# RN41-v14.net
KiCad netlist of a schematic drawn in EAGLE
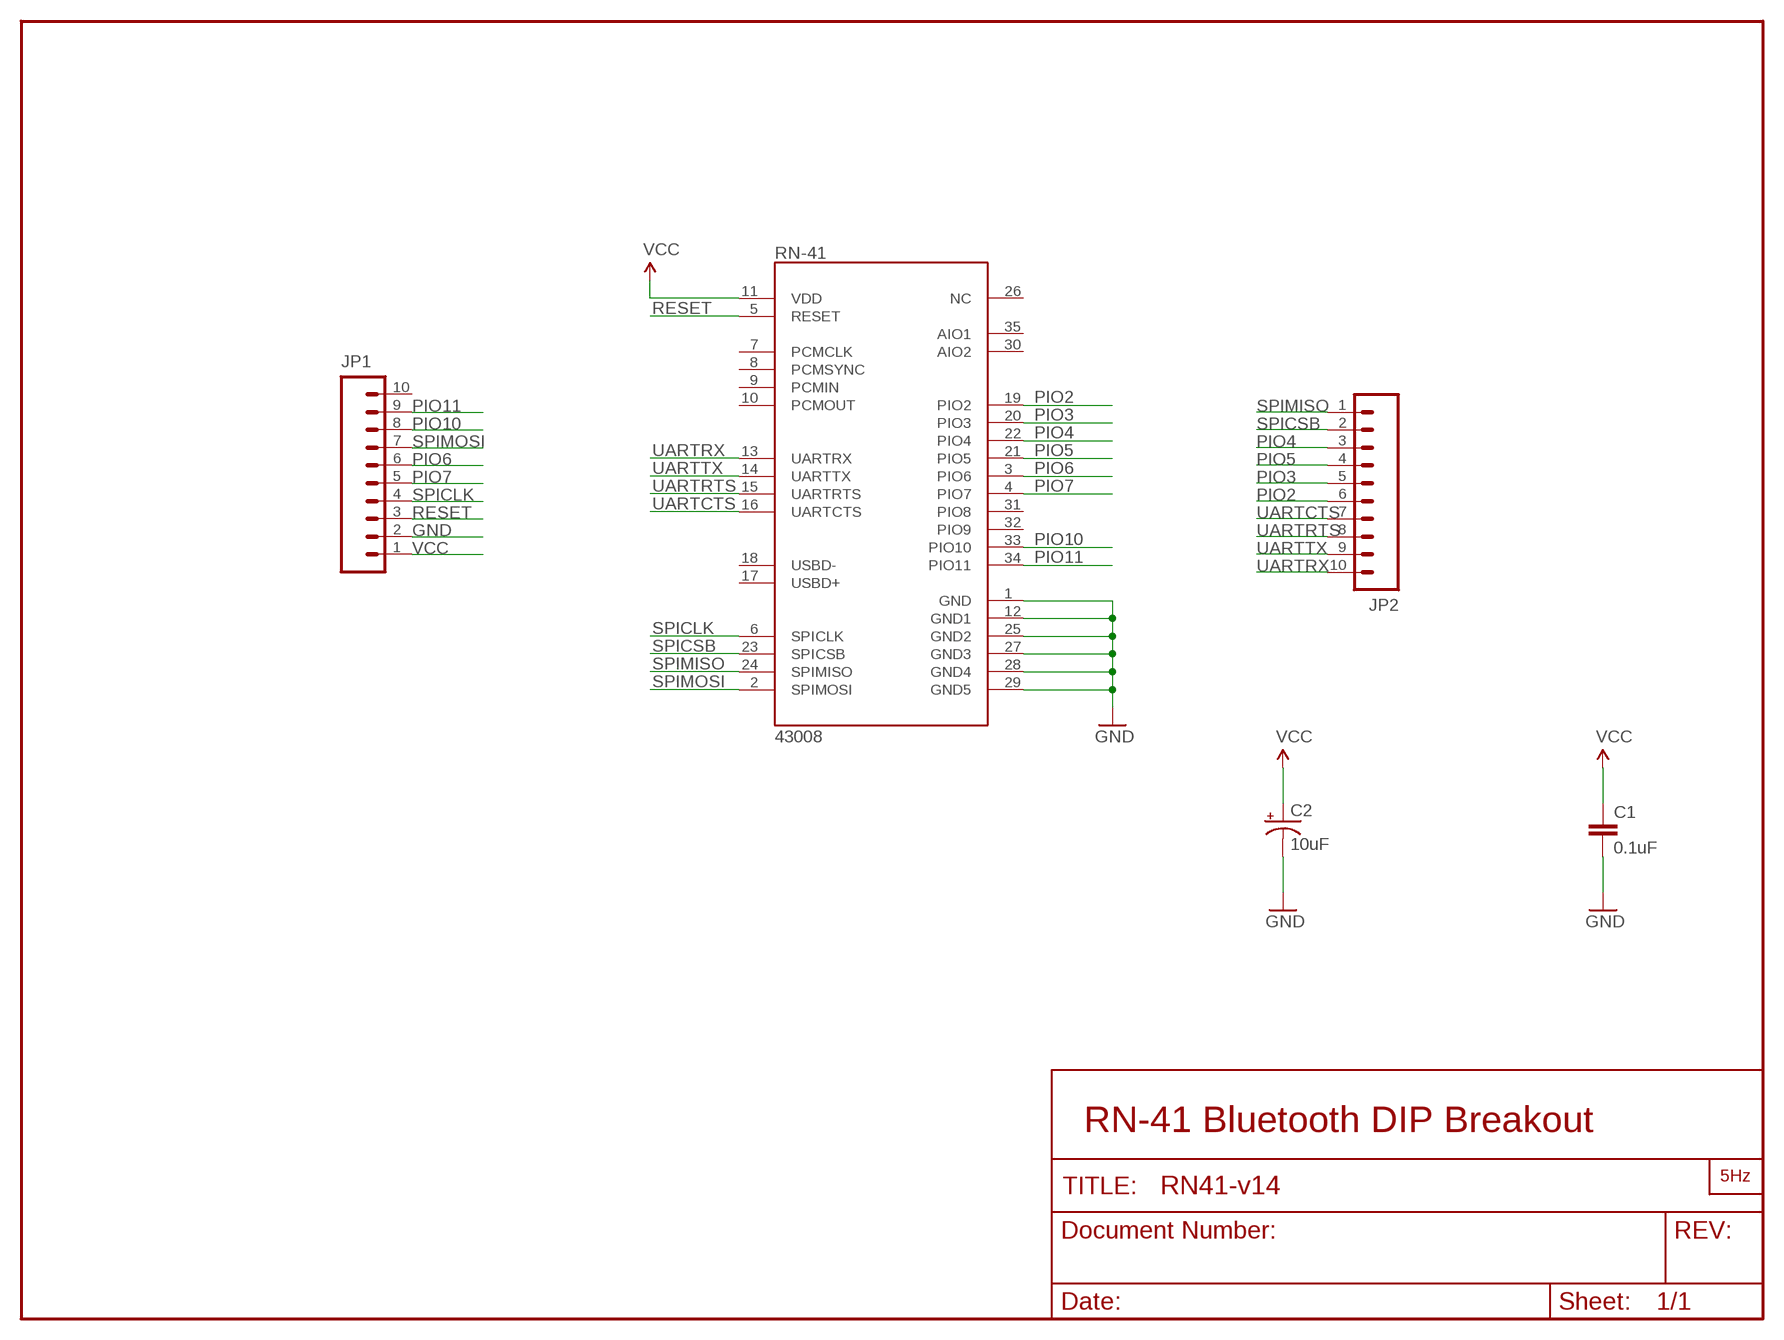
[diagram p0: schematic, sheet 1]

(export (version "E")
  (design (tool "Eeschema 10.0.6"))
  (components
    (comp (ref "C1")
      (value "0.1uF")
      (footprint "eagle-import:0603-CAP")
      (libsource (lib "eagle-import") (part "CAP0603-CAP"))
    )
    (comp (ref "C2")
      (value "10uF")
      (footprint "eagle-import:EIA3216")
      (libsource (lib "eagle-import") (part "CAP_POL1206"))
    )
    (comp (ref "JP1")
      (value "M10\"")
      (footprint "eagle-import:1X10")
      (libsource (lib "eagle-import") (part "M10{dblquote}"))
    )
    (comp (ref "JP2")
      (value "M10\"")
      (footprint "eagle-import:1X10")
      (libsource (lib "eagle-import") (part "M10{dblquote}"))
    )
    (comp (ref "RN-41")
      (value "43008")
      (footprint "eagle-import:RN41")
      (libsource (lib "eagle-import") (part "BLUETOOTH-RN41{dblquote}"))
    )
    (comp (ref "U$1")
      (value "LOGO2_SILKL10MM")
      (footprint "eagle-import:LARGO2_10MM")
      (libsource (lib "eagle-import") (part "LOGO2_SILKL10MM"))
    )
  )
  (nets
    (net (code "1") (name "/PIO2") (class "Default")
      (node (ref "JP2") (pin "6") (pinfunction "6_6") (pintype "passive"))
      (node (ref "RN-41") (pin "19") (pinfunction "PIO2_19") (pintype "bidirectional"))
    )
    (net (code "2") (name "/PIO3") (class "Default")
      (node (ref "JP2") (pin "5") (pinfunction "5_5") (pintype "passive"))
      (node (ref "RN-41") (pin "20") (pinfunction "PIO3_20") (pintype "bidirectional"))
    )
    (net (code "3") (name "/PIO4") (class "Default")
      (node (ref "JP2") (pin "3") (pinfunction "3_3") (pintype "passive"))
      (node (ref "RN-41") (pin "22") (pinfunction "PIO4_22") (pintype "bidirectional"))
    )
    (net (code "4") (name "/PIO5") (class "Default")
      (node (ref "JP2") (pin "4") (pinfunction "4_4") (pintype "passive"))
      (node (ref "RN-41") (pin "21") (pinfunction "PIO5_21") (pintype "bidirectional"))
    )
    (net (code "5") (name "/PIO6") (class "Default")
      (node (ref "JP1") (pin "6") (pinfunction "6_6") (pintype "passive"))
      (node (ref "RN-41") (pin "3") (pinfunction "PIO6_3") (pintype "bidirectional"))
    )
    (net (code "6") (name "/PIO7") (class "Default")
      (node (ref "JP1") (pin "5") (pinfunction "5_5") (pintype "passive"))
      (node (ref "RN-41") (pin "4") (pinfunction "PIO7_4") (pintype "bidirectional"))
    )
    (net (code "7") (name "/PIO10") (class "Default")
      (node (ref "JP1") (pin "8") (pinfunction "8_8") (pintype "passive"))
      (node (ref "RN-41") (pin "33") (pinfunction "PIO10_33") (pintype "bidirectional"))
    )
    (net (code "8") (name "/PIO11") (class "Default")
      (node (ref "JP1") (pin "9") (pinfunction "9_9") (pintype "passive"))
      (node (ref "RN-41") (pin "34") (pinfunction "PIO11_34") (pintype "bidirectional"))
    )
    (net (code "9") (name "/RESET") (class "Default")
      (node (ref "JP1") (pin "3") (pinfunction "3_3") (pintype "passive"))
      (node (ref "RN-41") (pin "5") (pinfunction "RESET_5") (pintype "bidirectional"))
    )
    (net (code "10") (name "/SPICLK") (class "Default")
      (node (ref "JP1") (pin "4") (pinfunction "4_4") (pintype "passive"))
      (node (ref "RN-41") (pin "6") (pinfunction "SPICLK_6") (pintype "bidirectional"))
    )
    (net (code "11") (name "/SPICSB") (class "Default")
      (node (ref "JP2") (pin "2") (pinfunction "2_2") (pintype "passive"))
      (node (ref "RN-41") (pin "23") (pinfunction "SPICSB_23") (pintype "bidirectional"))
    )
    (net (code "12") (name "/SPIMISO") (class "Default")
      (node (ref "JP2") (pin "1") (pinfunction "1_1") (pintype "passive"))
      (node (ref "RN-41") (pin "24") (pinfunction "SPIMISO_24") (pintype "bidirectional"))
    )
    (net (code "13") (name "/SPIMOSI") (class "Default")
      (node (ref "JP1") (pin "7") (pinfunction "7_7") (pintype "passive"))
      (node (ref "RN-41") (pin "2") (pinfunction "SPIMOSI_2") (pintype "bidirectional"))
    )
    (net (code "14") (name "/UARTCTS") (class "Default")
      (node (ref "JP2") (pin "7") (pinfunction "7_7") (pintype "passive"))
      (node (ref "RN-41") (pin "16") (pinfunction "UARTCTS_16") (pintype "bidirectional"))
    )
    (net (code "15") (name "/UARTRTS") (class "Default")
      (node (ref "JP2") (pin "8") (pinfunction "8_8") (pintype "passive"))
      (node (ref "RN-41") (pin "15") (pinfunction "UARTRTS_15") (pintype "bidirectional"))
    )
    (net (code "16") (name "/UARTRX") (class "Default")
      (node (ref "JP2") (pin "10") (pinfunction "10_10") (pintype "passive"))
      (node (ref "RN-41") (pin "13") (pinfunction "UARTRX_13") (pintype "bidirectional"))
    )
    (net (code "17") (name "/UARTTX") (class "Default")
      (node (ref "JP2") (pin "9") (pinfunction "9_9") (pintype "passive"))
      (node (ref "RN-41") (pin "14") (pinfunction "UARTTX_14") (pintype "bidirectional"))
    )
    (net (code "18") (name "GND") (class "Default")
      (node (ref "C1") (pin "2") (pinfunction "2_2") (pintype "passive"))
      (node (ref "C2") (pin "C") (pinfunction "-_C") (pintype "passive"))
      (node (ref "JP1") (pin "2") (pinfunction "2_2") (pintype "passive"))
      (node (ref "RN-41") (pin "1") (pinfunction "GND_1") (pintype "bidirectional"))
      (node (ref "RN-41") (pin "12") (pinfunction "GND1_12") (pintype "bidirectional"))
      (node (ref "RN-41") (pin "25") (pinfunction "GND2_25") (pintype "bidirectional"))
      (node (ref "RN-41") (pin "27") (pinfunction "GND3_27") (pintype "bidirectional"))
      (node (ref "RN-41") (pin "28") (pinfunction "GND4_28") (pintype "bidirectional"))
      (node (ref "RN-41") (pin "29") (pinfunction "GND5_29") (pintype "bidirectional"))
    )
    (net (code "19") (name "VCC") (class "Default")
      (node (ref "C1") (pin "1") (pinfunction "1_1") (pintype "passive"))
      (node (ref "C2") (pin "A") (pinfunction "+_A") (pintype "passive"))
      (node (ref "JP1") (pin "1") (pinfunction "1_1") (pintype "passive"))
      (node (ref "RN-41") (pin "11") (pinfunction "VDD_11") (pintype "bidirectional"))
    )
    (net (code "20") (name "unconnected-(JP1-Pad10)") (class "Default")
      (node (ref "JP1") (pin "10") (pinfunction "10_10") (pintype "passive"))
    )
    (net (code "21") (name "unconnected-(RN-41-AIO1-Pad35)") (class "Default")
      (node (ref "RN-41") (pin "35") (pinfunction "AIO1_35") (pintype "bidirectional"))
    )
    (net (code "22") (name "unconnected-(RN-41-AIO2-Pad30)") (class "Default")
      (node (ref "RN-41") (pin "30") (pinfunction "AIO2_30") (pintype "bidirectional"))
    )
    (net (code "23") (name "unconnected-(RN-41-NC-Pad26)") (class "Default")
      (node (ref "RN-41") (pin "26") (pinfunction "NC_26") (pintype "bidirectional"))
    )
    (net (code "24") (name "unconnected-(RN-41-PCMCLK-Pad7)") (class "Default")
      (node (ref "RN-41") (pin "7") (pinfunction "PCMCLK_7") (pintype "bidirectional"))
    )
    (net (code "25") (name "unconnected-(RN-41-PCMIN-Pad9)") (class "Default")
      (node (ref "RN-41") (pin "9") (pinfunction "PCMIN_9") (pintype "bidirectional"))
    )
    (net (code "26") (name "unconnected-(RN-41-PCMOUT-Pad10)") (class "Default")
      (node (ref "RN-41") (pin "10") (pinfunction "PCMOUT_10") (pintype "bidirectional"))
    )
    (net (code "27") (name "unconnected-(RN-41-PCMSYNC-Pad8)") (class "Default")
      (node (ref "RN-41") (pin "8") (pinfunction "PCMSYNC_8") (pintype "bidirectional"))
    )
    (net (code "28") (name "unconnected-(RN-41-PIO8-Pad31)") (class "Default")
      (node (ref "RN-41") (pin "31") (pinfunction "PIO8_31") (pintype "bidirectional"))
    )
    (net (code "29") (name "unconnected-(RN-41-PIO9-Pad32)") (class "Default")
      (node (ref "RN-41") (pin "32") (pinfunction "PIO9_32") (pintype "bidirectional"))
    )
    (net (code "30") (name "unconnected-(RN-41-USBD+-Pad17)") (class "Default")
      (node (ref "RN-41") (pin "17") (pinfunction "USBD+_17") (pintype "bidirectional"))
    )
    (net (code "31") (name "unconnected-(RN-41-USBD--Pad18)") (class "Default")
      (node (ref "RN-41") (pin "18") (pinfunction "USBD-_18") (pintype "bidirectional"))
    )
  )
)
